# Relay_Board_Rev1-3_-_EasyEDA.net
KiCad netlist of a schematic drawn in EasyEDA
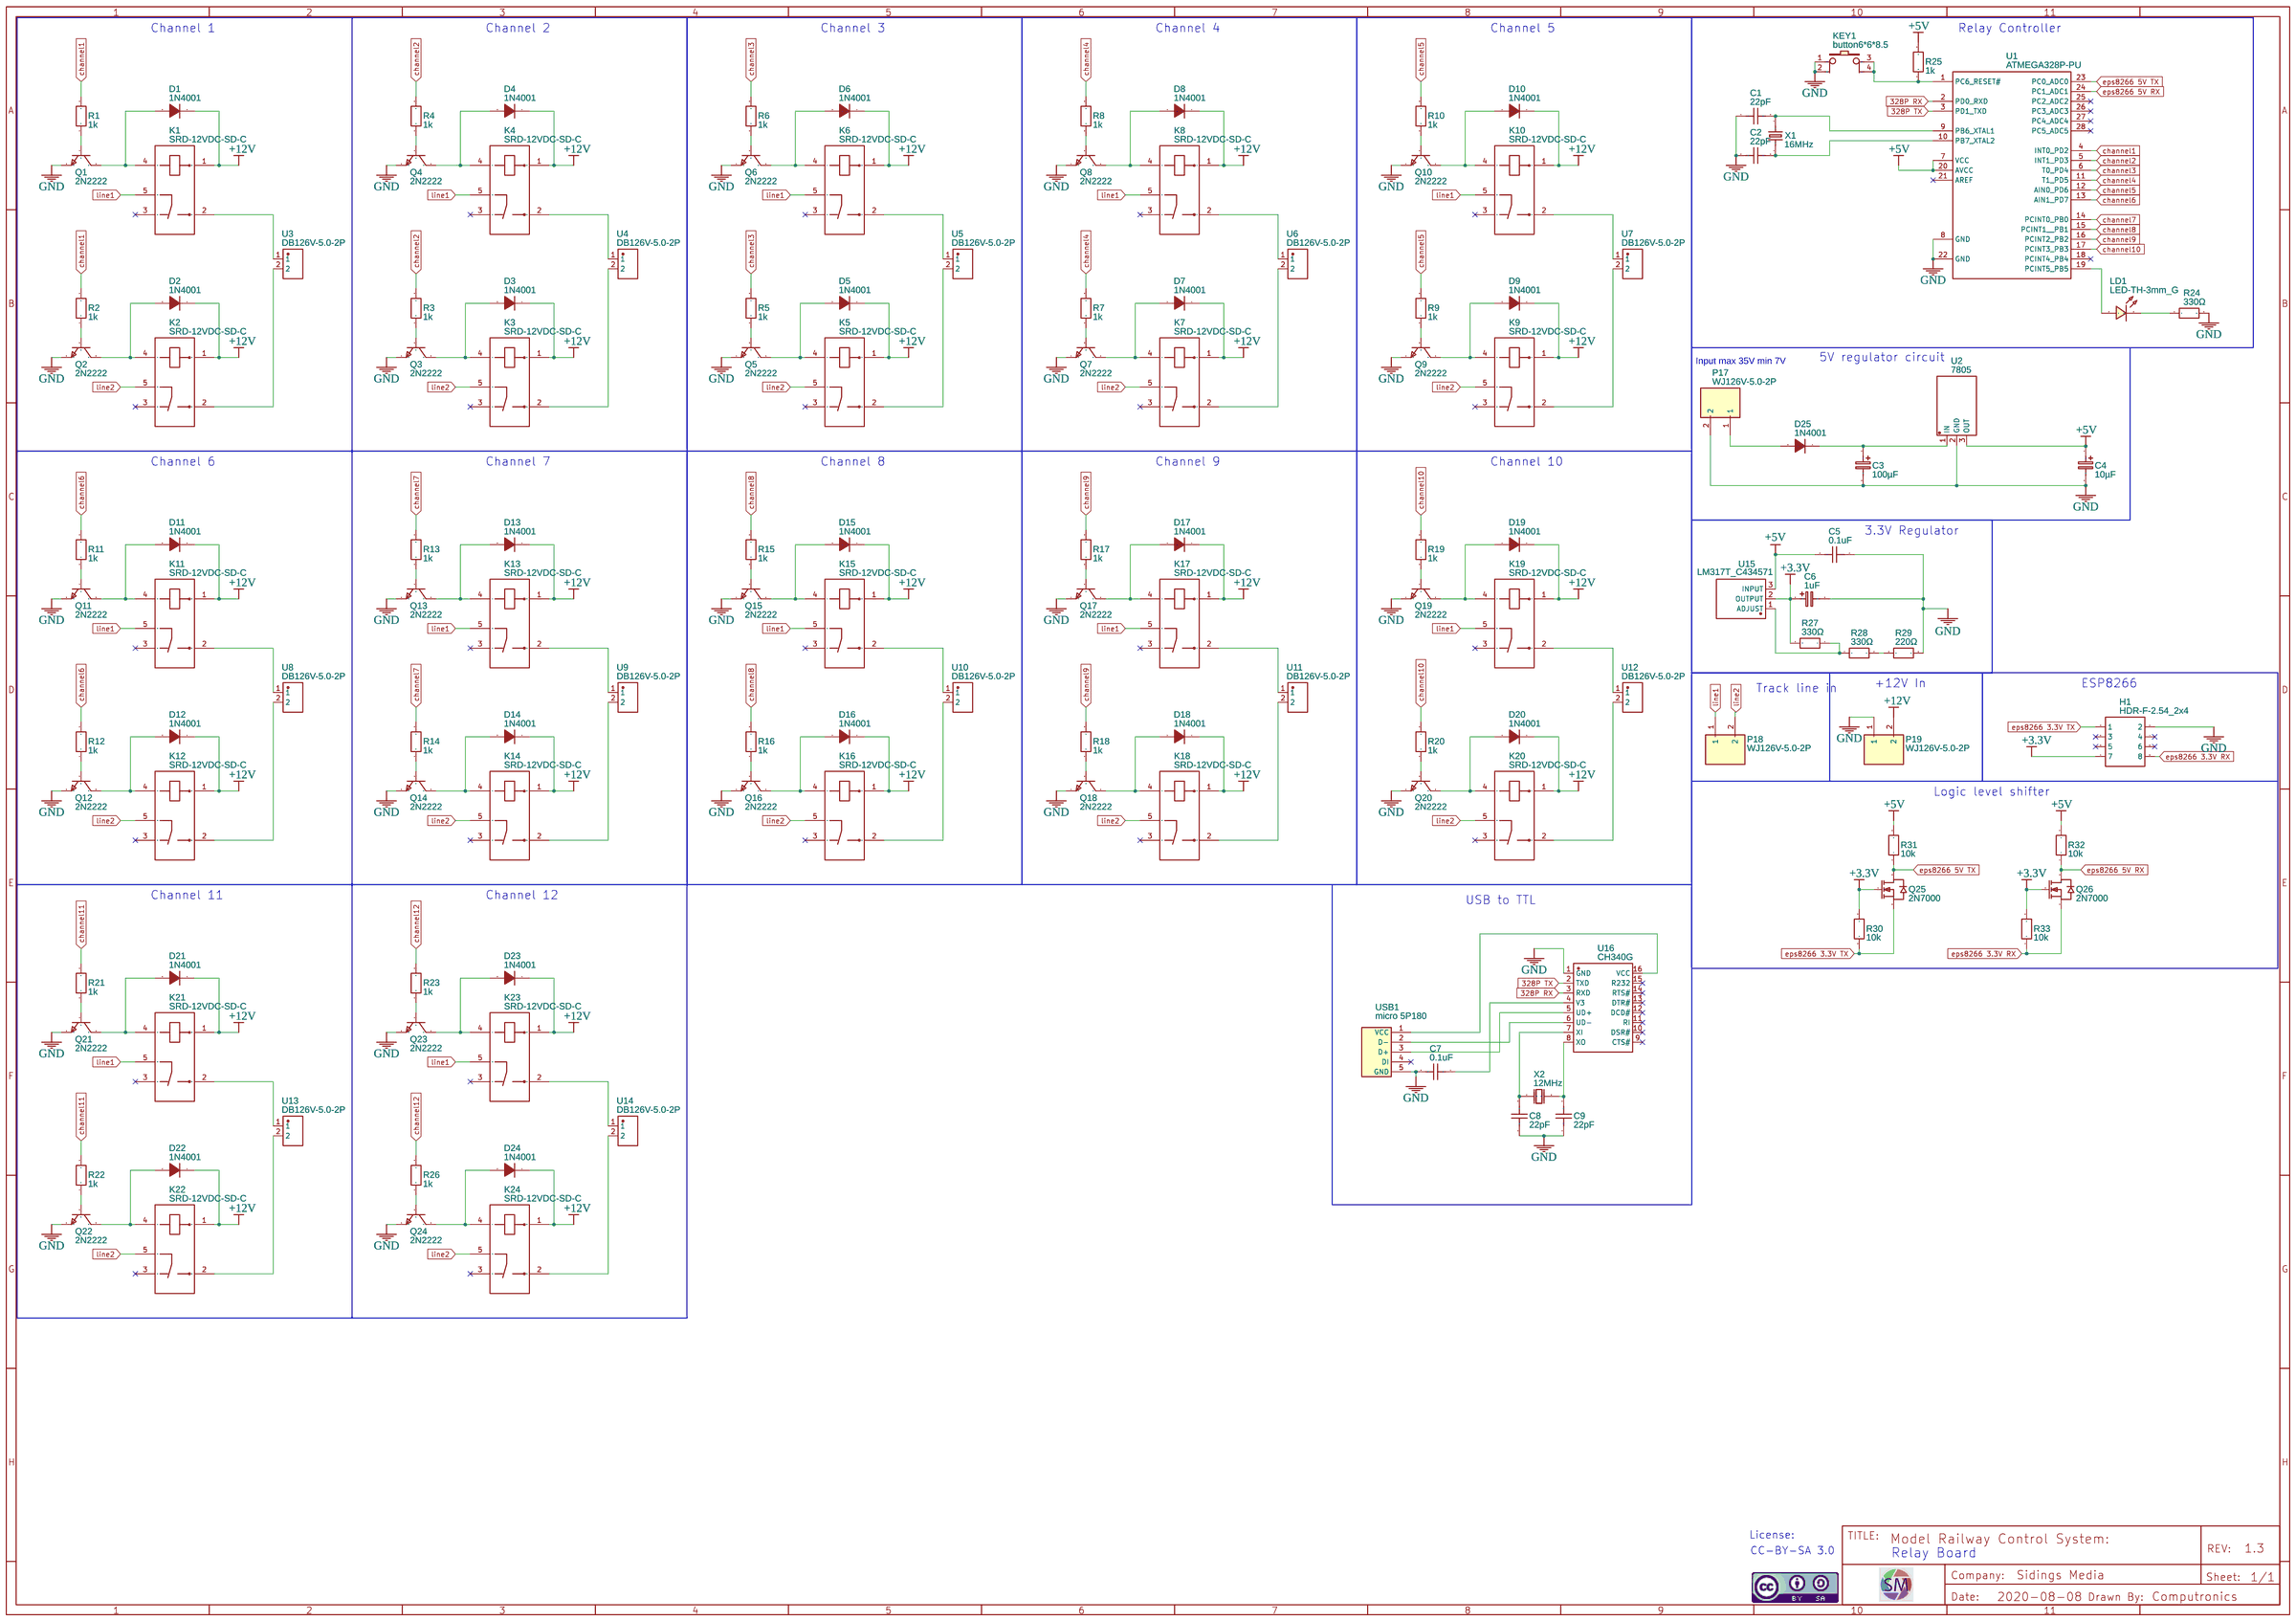
[diagram p0: schematic sheet]

(export (version "E")
  (design (tool "Eeschema 10.0.6"))
  (components
    (comp (ref "C1") (value "22pF") (libsource (lib "") (part "C_RAD-0.2_US")))
    (comp (ref "C2") (value "22pF") (libsource (lib "") (part "C_RAD-0.2_US")))
    (comp (ref "C3") (value "100µF") (libsource (lib "") (part "CE_TH_D3.0×F1.5_EU")))
    (comp (ref "C4") (value "10µF") (libsource (lib "") (part "CE_TH_D3.0×F1.5_EU_2")))
    (comp (ref "C5") (value "0.1uF") (libsource (lib "") (part "C_RAD-0.2_US_1")))
    (comp (ref "C6") (value "1uF") (libsource (lib "") (part "CE_TH_D3.0×F1.5_EU_1")))
    (comp (ref "C7") (value "0.1uF") (libsource (lib "") (part "C_RAD-0.2_US_1")))
    (comp (ref "C8") (value "22pF") (libsource (lib "") (part "C_RAD-0.2_US_2")))
    (comp (ref "C9") (value "22pF") (libsource (lib "") (part "C_RAD-0.2_US_2")))
    (comp (ref "D1")
      (value "1N4001")
      (fields (field (name "BOM_Supplier Part") "C82804"))
      (libsource (lib "") (part "1N4001"))
    )
    (comp (ref "D2")
      (value "1N4001")
      (fields (field (name "BOM_Supplier Part") "C82804"))
      (libsource (lib "") (part "1N4001"))
    )
    (comp (ref "D3")
      (value "1N4001")
      (fields (field (name "BOM_Supplier Part") "C82804"))
      (libsource (lib "") (part "1N4001"))
    )
    (comp (ref "D4")
      (value "1N4001")
      (fields (field (name "BOM_Supplier Part") "C82804"))
      (libsource (lib "") (part "1N4001"))
    )
    (comp (ref "D5")
      (value "1N4001")
      (fields (field (name "BOM_Supplier Part") "C82804"))
      (libsource (lib "") (part "1N4001"))
    )
    (comp (ref "D6")
      (value "1N4001")
      (fields (field (name "BOM_Supplier Part") "C82804"))
      (libsource (lib "") (part "1N4001"))
    )
    (comp (ref "D7")
      (value "1N4001")
      (fields (field (name "BOM_Supplier Part") "C82804"))
      (libsource (lib "") (part "1N4001"))
    )
    (comp (ref "D8")
      (value "1N4001")
      (fields (field (name "BOM_Supplier Part") "C82804"))
      (libsource (lib "") (part "1N4001"))
    )
    (comp (ref "D9")
      (value "1N4001")
      (fields (field (name "BOM_Supplier Part") "C82804"))
      (libsource (lib "") (part "1N4001"))
    )
    (comp (ref "D10")
      (value "1N4001")
      (fields (field (name "BOM_Supplier Part") "C82804"))
      (libsource (lib "") (part "1N4001"))
    )
    (comp (ref "D11")
      (value "1N4001")
      (fields (field (name "BOM_Supplier Part") "C82804"))
      (libsource (lib "") (part "1N4001"))
    )
    (comp (ref "D12")
      (value "1N4001")
      (fields (field (name "BOM_Supplier Part") "C82804"))
      (libsource (lib "") (part "1N4001"))
    )
    (comp (ref "D13")
      (value "1N4001")
      (fields (field (name "BOM_Supplier Part") "C82804"))
      (libsource (lib "") (part "1N4001"))
    )
    (comp (ref "D14")
      (value "1N4001")
      (fields (field (name "BOM_Supplier Part") "C82804"))
      (libsource (lib "") (part "1N4001"))
    )
    (comp (ref "D15")
      (value "1N4001")
      (fields (field (name "BOM_Supplier Part") "C82804"))
      (libsource (lib "") (part "1N4001"))
    )
    (comp (ref "D16")
      (value "1N4001")
      (fields (field (name "BOM_Supplier Part") "C82804"))
      (libsource (lib "") (part "1N4001"))
    )
    (comp (ref "D17")
      (value "1N4001")
      (fields (field (name "BOM_Supplier Part") "C82804"))
      (libsource (lib "") (part "1N4001"))
    )
    (comp (ref "D18")
      (value "1N4001")
      (fields (field (name "BOM_Supplier Part") "C82804"))
      (libsource (lib "") (part "1N4001"))
    )
    (comp (ref "D19")
      (value "1N4001")
      (fields (field (name "BOM_Supplier Part") "C82804"))
      (libsource (lib "") (part "1N4001"))
    )
    (comp (ref "D20")
      (value "1N4001")
      (fields (field (name "BOM_Supplier Part") "C82804"))
      (libsource (lib "") (part "1N4001"))
    )
    (comp (ref "D21")
      (value "1N4001")
      (fields (field (name "BOM_Supplier Part") "C82804"))
      (libsource (lib "") (part "1N4001"))
    )
    (comp (ref "D22")
      (value "1N4001")
      (fields (field (name "BOM_Supplier Part") "C82804"))
      (libsource (lib "") (part "1N4001"))
    )
    (comp (ref "D23")
      (value "1N4001")
      (fields (field (name "BOM_Supplier Part") "C82804"))
      (libsource (lib "") (part "1N4001"))
    )
    (comp (ref "D24")
      (value "1N4001")
      (fields (field (name "BOM_Supplier Part") "C82804"))
      (libsource (lib "") (part "1N4001"))
    )
    (comp (ref "D25")
      (value "1N4001")
      (fields (field (name "BOM_Supplier Part") "C82804"))
      (libsource (lib "") (part "1N4001"))
    )
    (comp (ref "H1")
      (value "HDR-F-2.54_2x4")
      (fields (field (name "BOM_Supplier Part") "C239344"))
      (libsource (lib "") (part "HDR-F-2.54_2x4"))
    )
    (comp (ref "K1")
      (value "SRD-12VDC-SD-C")
      (fields (field (name "BOM_Supplier Part") "C247843"))
      (libsource (lib "") (part "SRD-12VDC-SD-C"))
    )
    (comp (ref "K2")
      (value "SRD-12VDC-SD-C")
      (fields (field (name "BOM_Supplier Part") "C247843"))
      (libsource (lib "") (part "SRD-12VDC-SD-C"))
    )
    (comp (ref "K3")
      (value "SRD-12VDC-SD-C")
      (fields (field (name "BOM_Supplier Part") "C247843"))
      (libsource (lib "") (part "SRD-12VDC-SD-C"))
    )
    (comp (ref "K4")
      (value "SRD-12VDC-SD-C")
      (fields (field (name "BOM_Supplier Part") "C247843"))
      (libsource (lib "") (part "SRD-12VDC-SD-C"))
    )
    (comp (ref "K5")
      (value "SRD-12VDC-SD-C")
      (fields (field (name "BOM_Supplier Part") "C247843"))
      (libsource (lib "") (part "SRD-12VDC-SD-C"))
    )
    (comp (ref "K6")
      (value "SRD-12VDC-SD-C")
      (fields (field (name "BOM_Supplier Part") "C247843"))
      (libsource (lib "") (part "SRD-12VDC-SD-C"))
    )
    (comp (ref "K7")
      (value "SRD-12VDC-SD-C")
      (fields (field (name "BOM_Supplier Part") "C247843"))
      (libsource (lib "") (part "SRD-12VDC-SD-C"))
    )
    (comp (ref "K8")
      (value "SRD-12VDC-SD-C")
      (fields (field (name "BOM_Supplier Part") "C247843"))
      (libsource (lib "") (part "SRD-12VDC-SD-C"))
    )
    (comp (ref "K9")
      (value "SRD-12VDC-SD-C")
      (fields (field (name "BOM_Supplier Part") "C247843"))
      (libsource (lib "") (part "SRD-12VDC-SD-C"))
    )
    (comp (ref "K10")
      (value "SRD-12VDC-SD-C")
      (fields (field (name "BOM_Supplier Part") "C247843"))
      (libsource (lib "") (part "SRD-12VDC-SD-C"))
    )
    (comp (ref "K11")
      (value "SRD-12VDC-SD-C")
      (fields (field (name "BOM_Supplier Part") "C247843"))
      (libsource (lib "") (part "SRD-12VDC-SD-C"))
    )
    (comp (ref "K12")
      (value "SRD-12VDC-SD-C")
      (fields (field (name "BOM_Supplier Part") "C247843"))
      (libsource (lib "") (part "SRD-12VDC-SD-C"))
    )
    (comp (ref "K13")
      (value "SRD-12VDC-SD-C")
      (fields (field (name "BOM_Supplier Part") "C247843"))
      (libsource (lib "") (part "SRD-12VDC-SD-C"))
    )
    (comp (ref "K14")
      (value "SRD-12VDC-SD-C")
      (fields (field (name "BOM_Supplier Part") "C247843"))
      (libsource (lib "") (part "SRD-12VDC-SD-C"))
    )
    (comp (ref "K15")
      (value "SRD-12VDC-SD-C")
      (fields (field (name "BOM_Supplier Part") "C247843"))
      (libsource (lib "") (part "SRD-12VDC-SD-C"))
    )
    (comp (ref "K16")
      (value "SRD-12VDC-SD-C")
      (fields (field (name "BOM_Supplier Part") "C247843"))
      (libsource (lib "") (part "SRD-12VDC-SD-C"))
    )
    (comp (ref "K17")
      (value "SRD-12VDC-SD-C")
      (fields (field (name "BOM_Supplier Part") "C247843"))
      (libsource (lib "") (part "SRD-12VDC-SD-C"))
    )
    (comp (ref "K18")
      (value "SRD-12VDC-SD-C")
      (fields (field (name "BOM_Supplier Part") "C247843"))
      (libsource (lib "") (part "SRD-12VDC-SD-C"))
    )
    (comp (ref "K19")
      (value "SRD-12VDC-SD-C")
      (fields (field (name "BOM_Supplier Part") "C247843"))
      (libsource (lib "") (part "SRD-12VDC-SD-C"))
    )
    (comp (ref "K20")
      (value "SRD-12VDC-SD-C")
      (fields (field (name "BOM_Supplier Part") "C247843"))
      (libsource (lib "") (part "SRD-12VDC-SD-C"))
    )
    (comp (ref "K21")
      (value "SRD-12VDC-SD-C")
      (fields (field (name "BOM_Supplier Part") "C247843"))
      (libsource (lib "") (part "SRD-12VDC-SD-C"))
    )
    (comp (ref "K22")
      (value "SRD-12VDC-SD-C")
      (fields (field (name "BOM_Supplier Part") "C247843"))
      (libsource (lib "") (part "SRD-12VDC-SD-C"))
    )
    (comp (ref "K23")
      (value "SRD-12VDC-SD-C")
      (fields (field (name "BOM_Supplier Part") "C247843"))
      (libsource (lib "") (part "SRD-12VDC-SD-C"))
    )
    (comp (ref "K24")
      (value "SRD-12VDC-SD-C")
      (fields (field (name "BOM_Supplier Part") "C247843"))
      (libsource (lib "") (part "SRD-12VDC-SD-C"))
    )
    (comp (ref "KEY1")
      (value "button6*6*8.5")
      (fields (field (name "BOM_Supplier Part") "C59980"))
      (libsource (lib "") (part "button6*6*8.5"))
    )
    (comp (ref "LD1")
      (value "LED-TH-3mm_G")
      (fields
        (field (name "BOM_Manufacturer Part") "204-10SYGD/S530-E3")
        (field (name "BOM_Supplier Part") "C85161")
      )
      (libsource (lib "") (part "LED-TH-3mm_G"))
    )
    (comp (ref "P17")
      (value "WJ126V-5.0-2P")
      (fields (field (name "BOM_Supplier Part") "C8404"))
      (libsource (lib "") (part "WJ126V-5.0-2P_1"))
    )
    (comp (ref "P18")
      (value "WJ126V-5.0-2P")
      (fields (field (name "BOM_Supplier Part") "C8404"))
      (libsource (lib "") (part "WJ126V-5.0-2P"))
    )
    (comp (ref "P19")
      (value "WJ126V-5.0-2P")
      (fields (field (name "BOM_Supplier Part") "C8404"))
      (libsource (lib "") (part "WJ126V-5.0-2P"))
    )
    (comp (ref "Q1")
      (value "2N2222")
      (fields (field (name "BOM_Supplier Part") "C118536"))
      (libsource (lib "") (part "2N2222"))
    )
    (comp (ref "Q2")
      (value "2N2222")
      (fields (field (name "BOM_Supplier Part") "C118536"))
      (libsource (lib "") (part "2N2222"))
    )
    (comp (ref "Q3")
      (value "2N2222")
      (fields (field (name "BOM_Supplier Part") "C118536"))
      (libsource (lib "") (part "2N2222"))
    )
    (comp (ref "Q4")
      (value "2N2222")
      (fields (field (name "BOM_Supplier Part") "C118536"))
      (libsource (lib "") (part "2N2222"))
    )
    (comp (ref "Q5")
      (value "2N2222")
      (fields (field (name "BOM_Supplier Part") "C118536"))
      (libsource (lib "") (part "2N2222"))
    )
    (comp (ref "Q6")
      (value "2N2222")
      (fields (field (name "BOM_Supplier Part") "C118536"))
      (libsource (lib "") (part "2N2222"))
    )
    (comp (ref "Q7")
      (value "2N2222")
      (fields (field (name "BOM_Supplier Part") "C118536"))
      (libsource (lib "") (part "2N2222"))
    )
    (comp (ref "Q8")
      (value "2N2222")
      (fields (field (name "BOM_Supplier Part") "C118536"))
      (libsource (lib "") (part "2N2222"))
    )
    (comp (ref "Q9")
      (value "2N2222")
      (fields (field (name "BOM_Supplier Part") "C118536"))
      (libsource (lib "") (part "2N2222"))
    )
    (comp (ref "Q10")
      (value "2N2222")
      (fields (field (name "BOM_Supplier Part") "C118536"))
      (libsource (lib "") (part "2N2222"))
    )
    (comp (ref "Q11")
      (value "2N2222")
      (fields (field (name "BOM_Supplier Part") "C118536"))
      (libsource (lib "") (part "2N2222"))
    )
    (comp (ref "Q12")
      (value "2N2222")
      (fields (field (name "BOM_Supplier Part") "C118536"))
      (libsource (lib "") (part "2N2222"))
    )
    (comp (ref "Q13")
      (value "2N2222")
      (fields (field (name "BOM_Supplier Part") "C118536"))
      (libsource (lib "") (part "2N2222"))
    )
    (comp (ref "Q14")
      (value "2N2222")
      (fields (field (name "BOM_Supplier Part") "C118536"))
      (libsource (lib "") (part "2N2222"))
    )
    (comp (ref "Q15")
      (value "2N2222")
      (fields (field (name "BOM_Supplier Part") "C118536"))
      (libsource (lib "") (part "2N2222"))
    )
    (comp (ref "Q16")
      (value "2N2222")
      (fields (field (name "BOM_Supplier Part") "C118536"))
      (libsource (lib "") (part "2N2222"))
    )
    (comp (ref "Q17")
      (value "2N2222")
      (fields (field (name "BOM_Supplier Part") "C118536"))
      (libsource (lib "") (part "2N2222"))
    )
    (comp (ref "Q18")
      (value "2N2222")
      (fields (field (name "BOM_Supplier Part") "C118536"))
      (libsource (lib "") (part "2N2222"))
    )
    (comp (ref "Q19")
      (value "2N2222")
      (fields (field (name "BOM_Supplier Part") "C118536"))
      (libsource (lib "") (part "2N2222"))
    )
    (comp (ref "Q20")
      (value "2N2222")
      (fields (field (name "BOM_Supplier Part") "C118536"))
      (libsource (lib "") (part "2N2222"))
    )
    (comp (ref "Q21")
      (value "2N2222")
      (fields (field (name "BOM_Supplier Part") "C118536"))
      (libsource (lib "") (part "2N2222"))
    )
    (comp (ref "Q22")
      (value "2N2222")
      (fields (field (name "BOM_Supplier Part") "C118536"))
      (libsource (lib "") (part "2N2222"))
    )
    (comp (ref "Q23")
      (value "2N2222")
      (fields (field (name "BOM_Supplier Part") "C118536"))
      (libsource (lib "") (part "2N2222"))
    )
    (comp (ref "Q24")
      (value "2N2222")
      (fields (field (name "BOM_Supplier Part") "C118536"))
      (libsource (lib "") (part "2N2222"))
    )
    (comp (ref "Q25")
      (value "2N7000")
      (fields (field (name "BOM_Supplier Part") "C9114"))
      (libsource (lib "") (part "2N7000"))
    )
    (comp (ref "Q26")
      (value "2N7000")
      (fields (field (name "BOM_Supplier Part") "C9114"))
      (libsource (lib "") (part "2N7000"))
    )
    (comp (ref "R1") (value "1k") (libsource (lib "") (part "R_AXIAL-0.4_EU")))
    (comp (ref "R2") (value "1k") (libsource (lib "") (part "R_AXIAL-0.4_EU")))
    (comp (ref "R3") (value "1k") (libsource (lib "") (part "R_AXIAL-0.4_EU")))
    (comp (ref "R4") (value "1k") (libsource (lib "") (part "R_AXIAL-0.4_EU")))
    (comp (ref "R5") (value "1k") (libsource (lib "") (part "R_AXIAL-0.4_EU")))
    (comp (ref "R6") (value "1k") (libsource (lib "") (part "R_AXIAL-0.4_EU")))
    (comp (ref "R7") (value "1k") (libsource (lib "") (part "R_AXIAL-0.4_EU")))
    (comp (ref "R8") (value "1k") (libsource (lib "") (part "R_AXIAL-0.4_EU")))
    (comp (ref "R9") (value "1k") (libsource (lib "") (part "R_AXIAL-0.4_EU")))
    (comp (ref "R10") (value "1k") (libsource (lib "") (part "R_AXIAL-0.4_EU")))
    (comp (ref "R11") (value "1k") (libsource (lib "") (part "R_AXIAL-0.4_EU")))
    (comp (ref "R12") (value "1k") (libsource (lib "") (part "R_AXIAL-0.4_EU")))
    (comp (ref "R13") (value "1k") (libsource (lib "") (part "R_AXIAL-0.4_EU")))
    (comp (ref "R14") (value "1k") (libsource (lib "") (part "R_AXIAL-0.4_EU")))
    (comp (ref "R15") (value "1k") (libsource (lib "") (part "R_AXIAL-0.4_EU")))
    (comp (ref "R16") (value "1k") (libsource (lib "") (part "R_AXIAL-0.4_EU")))
    (comp (ref "R17") (value "1k") (libsource (lib "") (part "R_AXIAL-0.4_EU")))
    (comp (ref "R18") (value "1k") (libsource (lib "") (part "R_AXIAL-0.4_EU")))
    (comp (ref "R19") (value "1k") (libsource (lib "") (part "R_AXIAL-0.4_EU")))
    (comp (ref "R20") (value "1k") (libsource (lib "") (part "R_AXIAL-0.4_EU")))
    (comp (ref "R21") (value "1k") (libsource (lib "") (part "R_AXIAL-0.4_EU")))
    (comp (ref "R22") (value "1k") (libsource (lib "") (part "R_AXIAL-0.4_EU")))
    (comp (ref "R23") (value "1k") (libsource (lib "") (part "R_AXIAL-0.4_EU")))
    (comp (ref "R24") (value "330Ω") (libsource (lib "") (part "R_AXIAL-0.4_EU_1")))
    (comp (ref "R25") (value "1k") (libsource (lib "") (part "R_AXIAL-0.4_EU")))
    (comp (ref "R26") (value "1k") (libsource (lib "") (part "R_AXIAL-0.4_EU")))
    (comp (ref "R27") (value "330Ω") (libsource (lib "") (part "R_AXIAL-0.4_EU_2")))
    (comp (ref "R28") (value "330Ω") (libsource (lib "") (part "R_AXIAL-0.4_EU_1")))
    (comp (ref "R29") (value "220Ω") (libsource (lib "") (part "R_AXIAL-0.4_EU_1")))
    (comp (ref "R30") (value "10k") (libsource (lib "") (part "R_AXIAL-0.4_EU")))
    (comp (ref "R31") (value "10k") (libsource (lib "") (part "R_AXIAL-0.4_EU")))
    (comp (ref "R32") (value "10k") (libsource (lib "") (part "R_AXIAL-0.4_EU")))
    (comp (ref "R33") (value "10k") (libsource (lib "") (part "R_AXIAL-0.4_EU")))
    (comp (ref "U1")
      (value "ATMEGA328P-PU")
      (fields (field (name "BOM_Supplier Part") "C33901"))
      (libsource (lib "") (part "ATMEGA328P-PU"))
    )
    (comp (ref "U2")
      (value "7805")
      (fields (field (name "BOM_Supplier Part") "C305416"))
      (libsource (lib "") (part "7805"))
    )
    (comp (ref "U3")
      (value "DB126V-5.0-2P")
      (fields (field (name "BOM_Supplier Part") "C395849"))
      (libsource (lib "") (part "DB126V-5.0-2P"))
    )
    (comp (ref "U4")
      (value "DB126V-5.0-2P")
      (fields (field (name "BOM_Supplier Part") "C395849"))
      (libsource (lib "") (part "DB126V-5.0-2P"))
    )
    (comp (ref "U5")
      (value "DB126V-5.0-2P")
      (fields (field (name "BOM_Supplier Part") "C395849"))
      (libsource (lib "") (part "DB126V-5.0-2P"))
    )
    (comp (ref "U6")
      (value "DB126V-5.0-2P")
      (fields (field (name "BOM_Supplier Part") "C395849"))
      (libsource (lib "") (part "DB126V-5.0-2P"))
    )
    (comp (ref "U7")
      (value "DB126V-5.0-2P")
      (fields (field (name "BOM_Supplier Part") "C395849"))
      (libsource (lib "") (part "DB126V-5.0-2P"))
    )
    (comp (ref "U8")
      (value "DB126V-5.0-2P")
      (fields (field (name "BOM_Supplier Part") "C395849"))
      (libsource (lib "") (part "DB126V-5.0-2P"))
    )
    (comp (ref "U9")
      (value "DB126V-5.0-2P")
      (fields (field (name "BOM_Supplier Part") "C395849"))
      (libsource (lib "") (part "DB126V-5.0-2P"))
    )
    (comp (ref "U10")
      (value "DB126V-5.0-2P")
      (fields (field (name "BOM_Supplier Part") "C395849"))
      (libsource (lib "") (part "DB126V-5.0-2P"))
    )
    (comp (ref "U11")
      (value "DB126V-5.0-2P")
      (fields (field (name "BOM_Supplier Part") "C395849"))
      (libsource (lib "") (part "DB126V-5.0-2P"))
    )
    (comp (ref "U12")
      (value "DB126V-5.0-2P")
      (fields (field (name "BOM_Supplier Part") "C395849"))
      (libsource (lib "") (part "DB126V-5.0-2P"))
    )
    (comp (ref "U13")
      (value "DB126V-5.0-2P")
      (fields (field (name "BOM_Supplier Part") "C395849"))
      (libsource (lib "") (part "DB126V-5.0-2P"))
    )
    (comp (ref "U14")
      (value "DB126V-5.0-2P")
      (fields (field (name "BOM_Supplier Part") "C395849"))
      (libsource (lib "") (part "DB126V-5.0-2P"))
    )
    (comp (ref "U15")
      (value "LM317T_C434571")
      (fields (field (name "BOM_Manufacturer Part") "LM317T") (field (name "BOM_Supplier Part") "C434571"))
      (libsource (lib "") (part "LM317T_C434571"))
    )
    (comp (ref "U16")
      (value "CH340G")
      (fields (field (name "BOM_Supplier Part") "C14267"))
      (libsource (lib "") (part "CH340G"))
    )
    (comp (ref "USB1")
      (value "micro 5P180")
      (fields (field (name "BOM_Supplier Part") "C40941"))
      (libsource (lib "") (part "micro 5P180"))
    )
    (comp (ref "X1")
      (value "16MHz")
      (fields
        (field (name "BOM_Manufacturer Part") "XIHCELNANF-16MHZ")
        (field (name "BOM_Supplier Part") "C295075")
      )
      (libsource (lib "") (part "XIHCELNANF-16MHZ"))
    )
    (comp (ref "X2")
      (value "12MHz")
      (fields
        (field (name "BOM_Manufacturer Part") "49S-12.00-20-20-20/A")
        (field (name "BOM_Supplier Part") "C240914")
      )
      (libsource (lib "") (part "49S-12.00-20-20-20/A"))
    )
  )
  (nets
    (net (code "1") (name "+3.3V") (class "Default")
      (node (ref "C6") (pin "1") (pinfunction "1_1") (pintype "unspecified"))
      (node (ref "H1") (pin "7") (pinfunction "7_7") (pintype "unspecified"))
      (node (ref "Q25") (pin "2") (pinfunction "G_2") (pintype "unspecified"))
      (node (ref "Q26") (pin "2") (pinfunction "G_2") (pintype "unspecified"))
      (node (ref "R27") (pin "2") (pinfunction "2_2") (pintype "unspecified"))
      (node (ref "R30") (pin "2") (pinfunction "2_2") (pintype "unspecified"))
      (node (ref "R33") (pin "2") (pinfunction "2_2") (pintype "unspecified"))
      (node (ref "U15") (pin "2") (pinfunction "OUTPUT_2") (pintype "unspecified"))
    )
    (net (code "2") (name "+5V") (class "Default")
      (node (ref "C4") (pin "1") (pinfunction "1_1") (pintype "unspecified"))
      (node (ref "C5") (pin "2") (pinfunction "2_2") (pintype "unspecified"))
      (node (ref "R25") (pin "2") (pinfunction "2_2") (pintype "unspecified"))
      (node (ref "R31") (pin "2") (pinfunction "2_2") (pintype "unspecified"))
      (node (ref "R32") (pin "2") (pinfunction "2_2") (pintype "unspecified"))
      (node (ref "U1") (pin "20") (pinfunction "AVCC_20") (pintype "passive"))
      (node (ref "U1") (pin "7") (pinfunction "VCC_7") (pintype "passive"))
      (node (ref "U15") (pin "3") (pinfunction "INPUT_3") (pintype "unspecified"))
      (node (ref "U2") (pin "3") (pinfunction "OUT_3") (pintype "unspecified"))
    )
    (net (code "3") (name "+12V") (class "Default")
      (node (ref "D1") (pin "1") (pinfunction "K_1") (pintype "unspecified"))
      (node (ref "D10") (pin "1") (pinfunction "K_1") (pintype "unspecified"))
      (node (ref "D11") (pin "1") (pinfunction "K_1") (pintype "unspecified"))
      (node (ref "D12") (pin "1") (pinfunction "K_1") (pintype "unspecified"))
      (node (ref "D13") (pin "1") (pinfunction "K_1") (pintype "unspecified"))
      (node (ref "D14") (pin "1") (pinfunction "K_1") (pintype "unspecified"))
      (node (ref "D15") (pin "1") (pinfunction "K_1") (pintype "unspecified"))
      (node (ref "D16") (pin "1") (pinfunction "K_1") (pintype "unspecified"))
      (node (ref "D17") (pin "1") (pinfunction "K_1") (pintype "unspecified"))
      (node (ref "D18") (pin "1") (pinfunction "K_1") (pintype "unspecified"))
      (node (ref "D19") (pin "1") (pinfunction "K_1") (pintype "unspecified"))
      (node (ref "D2") (pin "1") (pinfunction "K_1") (pintype "unspecified"))
      (node (ref "D20") (pin "1") (pinfunction "K_1") (pintype "unspecified"))
      (node (ref "D21") (pin "1") (pinfunction "K_1") (pintype "unspecified"))
      (node (ref "D22") (pin "1") (pinfunction "K_1") (pintype "unspecified"))
      (node (ref "D23") (pin "1") (pinfunction "K_1") (pintype "unspecified"))
      (node (ref "D24") (pin "1") (pinfunction "K_1") (pintype "unspecified"))
      (node (ref "D3") (pin "1") (pinfunction "K_1") (pintype "unspecified"))
      (node (ref "D4") (pin "1") (pinfunction "K_1") (pintype "unspecified"))
      (node (ref "D5") (pin "1") (pinfunction "K_1") (pintype "unspecified"))
      (node (ref "D6") (pin "1") (pinfunction "K_1") (pintype "unspecified"))
      (node (ref "D7") (pin "1") (pinfunction "K_1") (pintype "unspecified"))
      (node (ref "D8") (pin "1") (pinfunction "K_1") (pintype "unspecified"))
      (node (ref "D9") (pin "1") (pinfunction "K_1") (pintype "unspecified"))
      (node (ref "K1") (pin "1") (pinfunction "1_1") (pintype "input"))
      (node (ref "K10") (pin "1") (pinfunction "1_1") (pintype "input"))
      (node (ref "K11") (pin "1") (pinfunction "1_1") (pintype "input"))
      (node (ref "K12") (pin "1") (pinfunction "1_1") (pintype "input"))
      (node (ref "K13") (pin "1") (pinfunction "1_1") (pintype "input"))
      (node (ref "K14") (pin "1") (pinfunction "1_1") (pintype "input"))
      (node (ref "K15") (pin "1") (pinfunction "1_1") (pintype "input"))
      (node (ref "K16") (pin "1") (pinfunction "1_1") (pintype "input"))
      (node (ref "K17") (pin "1") (pinfunction "1_1") (pintype "input"))
      (node (ref "K18") (pin "1") (pinfunction "1_1") (pintype "input"))
      (node (ref "K19") (pin "1") (pinfunction "1_1") (pintype "input"))
      (node (ref "K2") (pin "1") (pinfunction "1_1") (pintype "input"))
      (node (ref "K20") (pin "1") (pinfunction "1_1") (pintype "input"))
      (node (ref "K21") (pin "1") (pinfunction "1_1") (pintype "input"))
      (node (ref "K22") (pin "1") (pinfunction "1_1") (pintype "input"))
      (node (ref "K23") (pin "1") (pinfunction "1_1") (pintype "input"))
      (node (ref "K24") (pin "1") (pinfunction "1_1") (pintype "input"))
      (node (ref "K3") (pin "1") (pinfunction "1_1") (pintype "input"))
      (node (ref "K4") (pin "1") (pinfunction "1_1") (pintype "input"))
      (node (ref "K5") (pin "1") (pinfunction "1_1") (pintype "input"))
      (node (ref "K6") (pin "1") (pinfunction "1_1") (pintype "input"))
      (node (ref "K7") (pin "1") (pinfunction "1_1") (pintype "input"))
      (node (ref "K8") (pin "1") (pinfunction "1_1") (pintype "input"))
      (node (ref "K9") (pin "1") (pinfunction "1_1") (pintype "input"))
      (node (ref "P19") (pin "2") (pinfunction "2_2") (pintype "input"))
    )
    (net (code "4") (name "328P RX") (class "Default")
      (node (ref "U1") (pin "2") (pinfunction "PD0_RXD_2") (pintype "bidirectional"))
      (node (ref "U16") (pin "3") (pinfunction "RXD_3") (pintype "unspecified"))
    )
    (net (code "5") (name "328P TX") (class "Default")
      (node (ref "U1") (pin "3") (pinfunction "PD1_TXD_3") (pintype "bidirectional"))
      (node (ref "U16") (pin "2") (pinfunction "TXD_2") (pintype "unspecified"))
    )
    (net (code "6") (name "GND") (class "Default")
      (node (ref "C1") (pin "1") (pinfunction "1_1") (pintype "unspecified"))
      (node (ref "C2") (pin "1") (pinfunction "1_1") (pintype "unspecified"))
      (node (ref "C3") (pin "2") (pinfunction "2_2") (pintype "unspecified"))
      (node (ref "C4") (pin "2") (pinfunction "2_2") (pintype "unspecified"))
      (node (ref "C5") (pin "1") (pinfunction "1_1") (pintype "unspecified"))
      (node (ref "C6") (pin "2") (pinfunction "2_2") (pintype "unspecified"))
      (node (ref "C7") (pin "2") (pinfunction "2_2") (pintype "unspecified"))
      (node (ref "C8") (pin "1") (pinfunction "1_1") (pintype "unspecified"))
      (node (ref "C9") (pin "1") (pinfunction "1_1") (pintype "unspecified"))
      (node (ref "H1") (pin "2") (pinfunction "2_2") (pintype "unspecified"))
      (node (ref "KEY1") (pin "1") (pinfunction "1_1") (pintype "input"))
      (node (ref "KEY1") (pin "2") (pinfunction "2_2") (pintype "input"))
      (node (ref "P17") (pin "2") (pinfunction "2_2") (pintype "input"))
      (node (ref "P19") (pin "1") (pinfunction "1_1") (pintype "input"))
      (node (ref "Q1") (pin "1") (pinfunction "E_1") (pintype "unspecified"))
      (node (ref "Q10") (pin "1") (pinfunction "E_1") (pintype "unspecified"))
      (node (ref "Q11") (pin "1") (pinfunction "E_1") (pintype "unspecified"))
      (node (ref "Q12") (pin "1") (pinfunction "E_1") (pintype "unspecified"))
      (node (ref "Q13") (pin "1") (pinfunction "E_1") (pintype "unspecified"))
      (node (ref "Q14") (pin "1") (pinfunction "E_1") (pintype "unspecified"))
      (node (ref "Q15") (pin "1") (pinfunction "E_1") (pintype "unspecified"))
      (node (ref "Q16") (pin "1") (pinfunction "E_1") (pintype "unspecified"))
      (node (ref "Q17") (pin "1") (pinfunction "E_1") (pintype "unspecified"))
      (node (ref "Q18") (pin "1") (pinfunction "E_1") (pintype "unspecified"))
      (node (ref "Q19") (pin "1") (pinfunction "E_1") (pintype "unspecified"))
      (node (ref "Q2") (pin "1") (pinfunction "E_1") (pintype "unspecified"))
      (node (ref "Q20") (pin "1") (pinfunction "E_1") (pintype "unspecified"))
      (node (ref "Q21") (pin "1") (pinfunction "E_1") (pintype "unspecified"))
      (node (ref "Q22") (pin "1") (pinfunction "E_1") (pintype "unspecified"))
      (node (ref "Q23") (pin "1") (pinfunction "E_1") (pintype "unspecified"))
      (node (ref "Q24") (pin "1") (pinfunction "E_1") (pintype "unspecified"))
      (node (ref "Q3") (pin "1") (pinfunction "E_1") (pintype "unspecified"))
      (node (ref "Q4") (pin "1") (pinfunction "E_1") (pintype "unspecified"))
      (node (ref "Q5") (pin "1") (pinfunction "E_1") (pintype "unspecified"))
      (node (ref "Q6") (pin "1") (pinfunction "E_1") (pintype "unspecified"))
      (node (ref "Q7") (pin "1") (pinfunction "E_1") (pintype "unspecified"))
      (node (ref "Q8") (pin "1") (pinfunction "E_1") (pintype "unspecified"))
      (node (ref "Q9") (pin "1") (pinfunction "E_1") (pintype "unspecified"))
      (node (ref "R24") (pin "2") (pinfunction "2_2") (pintype "unspecified"))
      (node (ref "R29") (pin "2") (pinfunction "2_2") (pintype "unspecified"))
      (node (ref "U1") (pin "22") (pinfunction "GND_22") (pintype "passive"))
      (node (ref "U1") (pin "8") (pinfunction "GND_8") (pintype "passive"))
      (node (ref "U16") (pin "1") (pinfunction "GND_1") (pintype "unspecified"))
      (node (ref "U2") (pin "2") (pinfunction "GND_2") (pintype "unspecified"))
      (node (ref "USB1") (pin "5") (pinfunction "GND_5") (pintype "input"))
    )
    (net (code "7") (name "Net-(D1-A)") (class "Default")
      (node (ref "D1") (pin "2") (pinfunction "A_2") (pintype "unspecified"))
      (node (ref "K1") (pin "4") (pinfunction "4_4") (pintype "input"))
      (node (ref "Q1") (pin "3") (pinfunction "C_3") (pintype "unspecified"))
    )
    (net (code "8") (name "Net-(D2-A)") (class "Default")
      (node (ref "D2") (pin "2") (pinfunction "A_2") (pintype "unspecified"))
      (node (ref "K2") (pin "4") (pinfunction "4_4") (pintype "input"))
      (node (ref "Q2") (pin "3") (pinfunction "C_3") (pintype "unspecified"))
    )
    (net (code "9") (name "Net-(D3-A)") (class "Default")
      (node (ref "D3") (pin "2") (pinfunction "A_2") (pintype "unspecified"))
      (node (ref "K3") (pin "4") (pinfunction "4_4") (pintype "input"))
      (node (ref "Q3") (pin "3") (pinfunction "C_3") (pintype "unspecified"))
    )
    (net (code "10") (name "Net-(D4-A)") (class "Default")
      (node (ref "D4") (pin "2") (pinfunction "A_2") (pintype "unspecified"))
      (node (ref "K4") (pin "4") (pinfunction "4_4") (pintype "input"))
      (node (ref "Q4") (pin "3") (pinfunction "C_3") (pintype "unspecified"))
    )
    (net (code "11") (name "Net-(D5-A)") (class "Default")
      (node (ref "D5") (pin "2") (pinfunction "A_2") (pintype "unspecified"))
      (node (ref "K5") (pin "4") (pinfunction "4_4") (pintype "input"))
      (node (ref "Q5") (pin "3") (pinfunction "C_3") (pintype "unspecified"))
    )
    (net (code "12") (name "Net-(D6-A)") (class "Default")
      (node (ref "D6") (pin "2") (pinfunction "A_2") (pintype "unspecified"))
      (node (ref "K6") (pin "4") (pinfunction "4_4") (pintype "input"))
      (node (ref "Q6") (pin "3") (pinfunction "C_3") (pintype "unspecified"))
    )
    (net (code "13") (name "Net-(D7-A)") (class "Default")
      (node (ref "D7") (pin "2") (pinfunction "A_2") (pintype "unspecified"))
      (node (ref "K7") (pin "4") (pinfunction "4_4") (pintype "input"))
      (node (ref "Q7") (pin "3") (pinfunction "C_3") (pintype "unspecified"))
    )
    (net (code "14") (name "Net-(D8-A)") (class "Default")
      (node (ref "D8") (pin "2") (pinfunction "A_2") (pintype "unspecified"))
      (node (ref "K8") (pin "4") (pinfunction "4_4") (pintype "input"))
      (node (ref "Q8") (pin "3") (pinfunction "C_3") (pintype "unspecified"))
    )
    (net (code "15") (name "Net-(D9-A)") (class "Default")
      (node (ref "D9") (pin "2") (pinfunction "A_2") (pintype "unspecified"))
      (node (ref "K9") (pin "4") (pinfunction "4_4") (pintype "input"))
      (node (ref "Q9") (pin "3") (pinfunction "C_3") (pintype "unspecified"))
    )
    (net (code "16") (name "Net-(D10-A)") (class "Default")
      (node (ref "D10") (pin "2") (pinfunction "A_2") (pintype "unspecified"))
      (node (ref "K10") (pin "4") (pinfunction "4_4") (pintype "input"))
      (node (ref "Q10") (pin "3") (pinfunction "C_3") (pintype "unspecified"))
    )
    (net (code "17") (name "Net-(D11-A)") (class "Default")
      (node (ref "D11") (pin "2") (pinfunction "A_2") (pintype "unspecified"))
      (node (ref "K11") (pin "4") (pinfunction "4_4") (pintype "input"))
      (node (ref "Q11") (pin "3") (pinfunction "C_3") (pintype "unspecified"))
    )
    (net (code "18") (name "Net-(D12-A)") (class "Default")
      (node (ref "D12") (pin "2") (pinfunction "A_2") (pintype "unspecified"))
      (node (ref "K12") (pin "4") (pinfunction "4_4") (pintype "input"))
      (node (ref "Q12") (pin "3") (pinfunction "C_3") (pintype "unspecified"))
    )
    (net (code "19") (name "Net-(D13-A)") (class "Default")
      (node (ref "D13") (pin "2") (pinfunction "A_2") (pintype "unspecified"))
      (node (ref "K13") (pin "4") (pinfunction "4_4") (pintype "input"))
      (node (ref "Q13") (pin "3") (pinfunction "C_3") (pintype "unspecified"))
    )
    (net (code "20") (name "Net-(D14-A)") (class "Default")
      (node (ref "D14") (pin "2") (pinfunction "A_2") (pintype "unspecified"))
      (node (ref "K14") (pin "4") (pinfunction "4_4") (pintype "input"))
      (node (ref "Q14") (pin "3") (pinfunction "C_3") (pintype "unspecified"))
    )
    (net (code "21") (name "Net-(D15-A)") (class "Default")
      (node (ref "D15") (pin "2") (pinfunction "A_2") (pintype "unspecified"))
      (node (ref "K15") (pin "4") (pinfunction "4_4") (pintype "input"))
      (node (ref "Q15") (pin "3") (pinfunction "C_3") (pintype "unspecified"))
    )
    (net (code "22") (name "Net-(D16-A)") (class "Default")
      (node (ref "D16") (pin "2") (pinfunction "A_2") (pintype "unspecified"))
      (node (ref "K16") (pin "4") (pinfunction "4_4") (pintype "input"))
      (node (ref "Q16") (pin "3") (pinfunction "C_3") (pintype "unspecified"))
    )
    (net (code "23") (name "Net-(D17-A)") (class "Default")
      (node (ref "D17") (pin "2") (pinfunction "A_2") (pintype "unspecified"))
      (node (ref "K17") (pin "4") (pinfunction "4_4") (pintype "input"))
      (node (ref "Q17") (pin "3") (pinfunction "C_3") (pintype "unspecified"))
    )
    (net (code "24") (name "Net-(D18-A)") (class "Default")
      (node (ref "D18") (pin "2") (pinfunction "A_2") (pintype "unspecified"))
      (node (ref "K18") (pin "4") (pinfunction "4_4") (pintype "input"))
      (node (ref "Q18") (pin "3") (pinfunction "C_3") (pintype "unspecified"))
    )
    (net (code "25") (name "Net-(D19-A)") (class "Default")
      (node (ref "D19") (pin "2") (pinfunction "A_2") (pintype "unspecified"))
      (node (ref "K19") (pin "4") (pinfunction "4_4") (pintype "input"))
      (node (ref "Q19") (pin "3") (pinfunction "C_3") (pintype "unspecified"))
    )
    (net (code "26") (name "Net-(D20-A)") (class "Default")
      (node (ref "D20") (pin "2") (pinfunction "A_2") (pintype "unspecified"))
      (node (ref "K20") (pin "4") (pinfunction "4_4") (pintype "input"))
      (node (ref "Q20") (pin "3") (pinfunction "C_3") (pintype "unspecified"))
    )
    (net (code "27") (name "Net-(D21-A)") (class "Default")
      (node (ref "D21") (pin "2") (pinfunction "A_2") (pintype "unspecified"))
      (node (ref "K21") (pin "4") (pinfunction "4_4") (pintype "input"))
      (node (ref "Q21") (pin "3") (pinfunction "C_3") (pintype "unspecified"))
    )
    (net (code "28") (name "Net-(D22-A)") (class "Default")
      (node (ref "D22") (pin "2") (pinfunction "A_2") (pintype "unspecified"))
      (node (ref "K22") (pin "4") (pinfunction "4_4") (pintype "input"))
      (node (ref "Q22") (pin "3") (pinfunction "C_3") (pintype "unspecified"))
    )
    (net (code "29") (name "Net-(D23-A)") (class "Default")
      (node (ref "D23") (pin "2") (pinfunction "A_2") (pintype "unspecified"))
      (node (ref "K23") (pin "4") (pinfunction "4_4") (pintype "input"))
      (node (ref "Q23") (pin "3") (pinfunction "C_3") (pintype "unspecified"))
    )
    (net (code "30") (name "Net-(D24-A)") (class "Default")
      (node (ref "D24") (pin "2") (pinfunction "A_2") (pintype "unspecified"))
      (node (ref "K24") (pin "4") (pinfunction "4_4") (pintype "input"))
      (node (ref "Q24") (pin "3") (pinfunction "C_3") (pintype "unspecified"))
    )
    (net (code "31") (name "Net-(D25-A)") (class "Default")
      (node (ref "D25") (pin "2") (pinfunction "A_2") (pintype "unspecified"))
      (node (ref "P17") (pin "1") (pinfunction "1_1") (pintype "input"))
    )
    (net (code "32") (name "Net-(D25-K)") (class "Default")
      (node (ref "C3") (pin "1") (pinfunction "1_1") (pintype "unspecified"))
      (node (ref "D25") (pin "1") (pinfunction "K_1") (pintype "unspecified"))
      (node (ref "U2") (pin "1") (pinfunction "IN_1") (pintype "unspecified"))
    )
    (net (code "33") (name "Net-(K1-Pad2)") (class "Default")
      (node (ref "K1") (pin "2") (pinfunction "2_2") (pintype "input"))
      (node (ref "U3") (pin "1") (pinfunction "1_1") (pintype "unspecified"))
    )
    (net (code "34") (name "Net-(K2-Pad2)") (class "Default")
      (node (ref "K2") (pin "2") (pinfunction "2_2") (pintype "input"))
      (node (ref "U3") (pin "2") (pinfunction "2_2") (pintype "unspecified"))
    )
    (net (code "35") (name "Net-(K3-Pad2)") (class "Default")
      (node (ref "K3") (pin "2") (pinfunction "2_2") (pintype "input"))
      (node (ref "U4") (pin "2") (pinfunction "2_2") (pintype "unspecified"))
    )
    (net (code "36") (name "Net-(K4-Pad2)") (class "Default")
      (node (ref "K4") (pin "2") (pinfunction "2_2") (pintype "input"))
      (node (ref "U4") (pin "1") (pinfunction "1_1") (pintype "unspecified"))
    )
    (net (code "37") (name "Net-(K5-Pad2)") (class "Default")
      (node (ref "K5") (pin "2") (pinfunction "2_2") (pintype "input"))
      (node (ref "U5") (pin "2") (pinfunction "2_2") (pintype "unspecified"))
    )
    (net (code "38") (name "Net-(K6-Pad2)") (class "Default")
      (node (ref "K6") (pin "2") (pinfunction "2_2") (pintype "input"))
      (node (ref "U5") (pin "1") (pinfunction "1_1") (pintype "unspecified"))
    )
    (net (code "39") (name "Net-(K7-Pad2)") (class "Default")
      (node (ref "K7") (pin "2") (pinfunction "2_2") (pintype "input"))
      (node (ref "U6") (pin "2") (pinfunction "2_2") (pintype "unspecified"))
    )
    (net (code "40") (name "Net-(K8-Pad2)") (class "Default")
      (node (ref "K8") (pin "2") (pinfunction "2_2") (pintype "input"))
      (node (ref "U6") (pin "1") (pinfunction "1_1") (pintype "unspecified"))
    )
    (net (code "41") (name "Net-(K9-Pad2)") (class "Default")
      (node (ref "K9") (pin "2") (pinfunction "2_2") (pintype "input"))
      (node (ref "U7") (pin "2") (pinfunction "2_2") (pintype "unspecified"))
    )
    (net (code "42") (name "Net-(K10-Pad2)") (class "Default")
      (node (ref "K10") (pin "2") (pinfunction "2_2") (pintype "input"))
      (node (ref "U7") (pin "1") (pinfunction "1_1") (pintype "unspecified"))
    )
    (net (code "43") (name "Net-(K11-Pad2)") (class "Default")
      (node (ref "K11") (pin "2") (pinfunction "2_2") (pintype "input"))
      (node (ref "U8") (pin "1") (pinfunction "1_1") (pintype "unspecified"))
    )
    (net (code "44") (name "Net-(K12-Pad2)") (class "Default")
      (node (ref "K12") (pin "2") (pinfunction "2_2") (pintype "input"))
      (node (ref "U8") (pin "2") (pinfunction "2_2") (pintype "unspecified"))
    )
    (net (code "45") (name "Net-(K13-Pad2)") (class "Default")
      (node (ref "K13") (pin "2") (pinfunction "2_2") (pintype "input"))
      (node (ref "U9") (pin "1") (pinfunction "1_1") (pintype "unspecified"))
    )
    (net (code "46") (name "Net-(K14-Pad2)") (class "Default")
      (node (ref "K14") (pin "2") (pinfunction "2_2") (pintype "input"))
      (node (ref "U9") (pin "2") (pinfunction "2_2") (pintype "unspecified"))
    )
    (net (code "47") (name "Net-(K15-Pad2)") (class "Default")
      (node (ref "K15") (pin "2") (pinfunction "2_2") (pintype "input"))
      (node (ref "U10") (pin "1") (pinfunction "1_1") (pintype "unspecified"))
    )
    (net (code "48") (name "Net-(K16-Pad2)") (class "Default")
      (node (ref "K16") (pin "2") (pinfunction "2_2") (pintype "input"))
      (node (ref "U10") (pin "2") (pinfunction "2_2") (pintype "unspecified"))
    )
    (net (code "49") (name "Net-(K17-Pad2)") (class "Default")
      (node (ref "K17") (pin "2") (pinfunction "2_2") (pintype "input"))
      (node (ref "U11") (pin "1") (pinfunction "1_1") (pintype "unspecified"))
    )
    (net (code "50") (name "Net-(K18-Pad2)") (class "Default")
      (node (ref "K18") (pin "2") (pinfunction "2_2") (pintype "input"))
      (node (ref "U11") (pin "2") (pinfunction "2_2") (pintype "unspecified"))
    )
    (net (code "51") (name "Net-(K19-Pad2)") (class "Default")
      (node (ref "K19") (pin "2") (pinfunction "2_2") (pintype "input"))
      (node (ref "U12") (pin "1") (pinfunction "1_1") (pintype "unspecified"))
    )
    (net (code "52") (name "Net-(K20-Pad2)") (class "Default")
      (node (ref "K20") (pin "2") (pinfunction "2_2") (pintype "input"))
      (node (ref "U12") (pin "2") (pinfunction "2_2") (pintype "unspecified"))
    )
    (net (code "53") (name "Net-(K21-Pad2)") (class "Default")
      (node (ref "K21") (pin "2") (pinfunction "2_2") (pintype "input"))
      (node (ref "U13") (pin "1") (pinfunction "1_1") (pintype "unspecified"))
    )
    (net (code "54") (name "Net-(K22-Pad2)") (class "Default")
      (node (ref "K22") (pin "2") (pinfunction "2_2") (pintype "input"))
      (node (ref "U13") (pin "2") (pinfunction "2_2") (pintype "unspecified"))
    )
    (net (code "55") (name "Net-(K23-Pad2)") (class "Default")
      (node (ref "K23") (pin "2") (pinfunction "2_2") (pintype "input"))
      (node (ref "U14") (pin "1") (pinfunction "1_1") (pintype "unspecified"))
    )
    (net (code "56") (name "Net-(K24-Pad2)") (class "Default")
      (node (ref "K24") (pin "2") (pinfunction "2_2") (pintype "input"))
      (node (ref "U14") (pin "2") (pinfunction "2_2") (pintype "unspecified"))
    )
    (net (code "57") (name "Net-(LD1-Pad2)") (class "Default")
      (node (ref "LD1") (pin "2") (pinfunction "2_2") (pintype "unspecified"))
      (node (ref "R24") (pin "1") (pinfunction "1_1") (pintype "unspecified"))
    )
    (net (code "58") (name "Net-(Q1-B)") (class "Default")
      (node (ref "Q1") (pin "2") (pinfunction "B_2") (pintype "unspecified"))
      (node (ref "R1") (pin "1") (pinfunction "1_1") (pintype "unspecified"))
    )
    (net (code "59") (name "Net-(Q2-B)") (class "Default")
      (node (ref "Q2") (pin "2") (pinfunction "B_2") (pintype "unspecified"))
      (node (ref "R2") (pin "1") (pinfunction "1_1") (pintype "unspecified"))
    )
    (net (code "60") (name "Net-(Q3-B)") (class "Default")
      (node (ref "Q3") (pin "2") (pinfunction "B_2") (pintype "unspecified"))
      (node (ref "R3") (pin "1") (pinfunction "1_1") (pintype "unspecified"))
    )
    (net (code "61") (name "Net-(Q4-B)") (class "Default")
      (node (ref "Q4") (pin "2") (pinfunction "B_2") (pintype "unspecified"))
      (node (ref "R4") (pin "1") (pinfunction "1_1") (pintype "unspecified"))
    )
    (net (code "62") (name "Net-(Q5-B)") (class "Default")
      (node (ref "Q5") (pin "2") (pinfunction "B_2") (pintype "unspecified"))
      (node (ref "R5") (pin "1") (pinfunction "1_1") (pintype "unspecified"))
    )
    (net (code "63") (name "Net-(Q6-B)") (class "Default")
      (node (ref "Q6") (pin "2") (pinfunction "B_2") (pintype "unspecified"))
      (node (ref "R6") (pin "1") (pinfunction "1_1") (pintype "unspecified"))
    )
    (net (code "64") (name "Net-(Q7-B)") (class "Default")
      (node (ref "Q7") (pin "2") (pinfunction "B_2") (pintype "unspecified"))
      (node (ref "R7") (pin "1") (pinfunction "1_1") (pintype "unspecified"))
    )
    (net (code "65") (name "Net-(Q8-B)") (class "Default")
      (node (ref "Q8") (pin "2") (pinfunction "B_2") (pintype "unspecified"))
      (node (ref "R8") (pin "1") (pinfunction "1_1") (pintype "unspecified"))
    )
    (net (code "66") (name "Net-(Q9-B)") (class "Default")
      (node (ref "Q9") (pin "2") (pinfunction "B_2") (pintype "unspecified"))
      (node (ref "R9") (pin "1") (pinfunction "1_1") (pintype "unspecified"))
    )
    (net (code "67") (name "Net-(Q10-B)") (class "Default")
      (node (ref "Q10") (pin "2") (pinfunction "B_2") (pintype "unspecified"))
      (node (ref "R10") (pin "1") (pinfunction "1_1") (pintype "unspecified"))
    )
    (net (code "68") (name "Net-(Q11-B)") (class "Default")
      (node (ref "Q11") (pin "2") (pinfunction "B_2") (pintype "unspecified"))
      (node (ref "R11") (pin "1") (pinfunction "1_1") (pintype "unspecified"))
    )
    (net (code "69") (name "Net-(Q12-B)") (class "Default")
      (node (ref "Q12") (pin "2") (pinfunction "B_2") (pintype "unspecified"))
      (node (ref "R12") (pin "1") (pinfunction "1_1") (pintype "unspecified"))
    )
    (net (code "70") (name "Net-(Q13-B)") (class "Default")
      (node (ref "Q13") (pin "2") (pinfunction "B_2") (pintype "unspecified"))
      (node (ref "R13") (pin "1") (pinfunction "1_1") (pintype "unspecified"))
    )
    (net (code "71") (name "Net-(Q14-B)") (class "Default")
      (node (ref "Q14") (pin "2") (pinfunction "B_2") (pintype "unspecified"))
      (node (ref "R14") (pin "1") (pinfunction "1_1") (pintype "unspecified"))
    )
    (net (code "72") (name "Net-(Q15-B)") (class "Default")
      (node (ref "Q15") (pin "2") (pinfunction "B_2") (pintype "unspecified"))
      (node (ref "R15") (pin "1") (pinfunction "1_1") (pintype "unspecified"))
    )
    (net (code "73") (name "Net-(Q16-B)") (class "Default")
      (node (ref "Q16") (pin "2") (pinfunction "B_2") (pintype "unspecified"))
      (node (ref "R16") (pin "1") (pinfunction "1_1") (pintype "unspecified"))
    )
    (net (code "74") (name "Net-(Q17-B)") (class "Default")
      (node (ref "Q17") (pin "2") (pinfunction "B_2") (pintype "unspecified"))
      (node (ref "R17") (pin "1") (pinfunction "1_1") (pintype "unspecified"))
    )
    (net (code "75") (name "Net-(Q18-B)") (class "Default")
      (node (ref "Q18") (pin "2") (pinfunction "B_2") (pintype "unspecified"))
      (node (ref "R18") (pin "1") (pinfunction "1_1") (pintype "unspecified"))
    )
    (net (code "76") (name "Net-(Q19-B)") (class "Default")
      (node (ref "Q19") (pin "2") (pinfunction "B_2") (pintype "unspecified"))
      (node (ref "R19") (pin "1") (pinfunction "1_1") (pintype "unspecified"))
    )
    (net (code "77") (name "Net-(Q20-B)") (class "Default")
      (node (ref "Q20") (pin "2") (pinfunction "B_2") (pintype "unspecified"))
      (node (ref "R20") (pin "1") (pinfunction "1_1") (pintype "unspecified"))
    )
    (net (code "78") (name "Net-(Q21-B)") (class "Default")
      (node (ref "Q21") (pin "2") (pinfunction "B_2") (pintype "unspecified"))
      (node (ref "R21") (pin "1") (pinfunction "1_1") (pintype "unspecified"))
    )
    (net (code "79") (name "Net-(Q22-B)") (class "Default")
      (node (ref "Q22") (pin "2") (pinfunction "B_2") (pintype "unspecified"))
      (node (ref "R22") (pin "1") (pinfunction "1_1") (pintype "unspecified"))
    )
    (net (code "80") (name "Net-(Q23-B)") (class "Default")
      (node (ref "Q23") (pin "2") (pinfunction "B_2") (pintype "unspecified"))
      (node (ref "R23") (pin "1") (pinfunction "1_1") (pintype "unspecified"))
    )
    (net (code "81") (name "Net-(Q24-B)") (class "Default")
      (node (ref "Q24") (pin "2") (pinfunction "B_2") (pintype "unspecified"))
      (node (ref "R26") (pin "1") (pinfunction "1_1") (pintype "unspecified"))
    )
    (net (code "82") (name "Net-(R28-Pad2)") (class "Default")
      (node (ref "R28") (pin "2") (pinfunction "2_2") (pintype "unspecified"))
      (node (ref "R29") (pin "1") (pinfunction "1_1") (pintype "unspecified"))
    )
    (net (code "83") (name "Net-(U1-PB6_XTAL1)") (class "Default")
      (node (ref "C1") (pin "2") (pinfunction "2_2") (pintype "unspecified"))
      (node (ref "U1") (pin "9") (pinfunction "PB6_XTAL1_9") (pintype "bidirectional"))
      (node (ref "X1") (pin "1") (pinfunction "1_1") (pintype "unspecified"))
    )
    (net (code "84") (name "Net-(U1-PB7_XTAL2)") (class "Default")
      (node (ref "C2") (pin "2") (pinfunction "2_2") (pintype "unspecified"))
      (node (ref "U1") (pin "10") (pinfunction "PB7_XTAL2_10") (pintype "bidirectional"))
      (node (ref "X1") (pin "2") (pinfunction "2_2") (pintype "unspecified"))
    )
    (net (code "85") (name "Net-(U1-PC6_RESET#)") (class "Default")
      (node (ref "KEY1") (pin "3") (pinfunction "3_3") (pintype "input"))
      (node (ref "KEY1") (pin "4") (pinfunction "4_4") (pintype "input"))
      (node (ref "R25") (pin "1") (pinfunction "1_1") (pintype "unspecified"))
      (node (ref "U1") (pin "1") (pinfunction "PC6_RESET#_1") (pintype "bidirectional"))
    )
    (net (code "86") (name "Net-(U1-PCINT5_PB5)") (class "Default")
      (node (ref "LD1") (pin "1") (pinfunction "1_1") (pintype "unspecified"))
      (node (ref "U1") (pin "19") (pinfunction "PCINT5_PB5_19") (pintype "bidirectional"))
    )
    (net (code "87") (name "Net-(U15-ADJUST)") (class "Default")
      (node (ref "R27") (pin "1") (pinfunction "1_1") (pintype "unspecified"))
      (node (ref "R28") (pin "1") (pinfunction "1_1") (pintype "unspecified"))
      (node (ref "U15") (pin "1") (pinfunction "ADJUST_1") (pintype "unspecified"))
    )
    (net (code "88") (name "Net-(U16-UD+)") (class "Default")
      (node (ref "U16") (pin "5") (pinfunction "UD+_5") (pintype "unspecified"))
      (node (ref "USB1") (pin "3") (pinfunction "D+_3") (pintype "input"))
    )
    (net (code "89") (name "Net-(U16-UD-)") (class "Default")
      (node (ref "U16") (pin "6") (pinfunction "UD-_6") (pintype "unspecified"))
      (node (ref "USB1") (pin "2") (pinfunction "D-_2") (pintype "input"))
    )
    (net (code "90") (name "Net-(U16-V3)") (class "Default")
      (node (ref "C7") (pin "1") (pinfunction "1_1") (pintype "unspecified"))
      (node (ref "U16") (pin "4") (pinfunction "V3_4") (pintype "unspecified"))
    )
    (net (code "91") (name "Net-(U16-VCC)") (class "Default")
      (node (ref "U16") (pin "16") (pinfunction "VCC_16") (pintype "unspecified"))
      (node (ref "USB1") (pin "1") (pinfunction "VCC_1") (pintype "input"))
    )
    (net (code "92") (name "Net-(U16-XI)") (class "Default")
      (node (ref "C8") (pin "2") (pinfunction "2_2") (pintype "unspecified"))
      (node (ref "U16") (pin "7") (pinfunction "XI_7") (pintype "unspecified"))
      (node (ref "X2") (pin "1") (pinfunction "OSC1_1") (pintype "input"))
    )
    (net (code "93") (name "Net-(U16-XO)") (class "Default")
      (node (ref "C9") (pin "2") (pinfunction "2_2") (pintype "unspecified"))
      (node (ref "U16") (pin "8") (pinfunction "XO_8") (pintype "unspecified"))
      (node (ref "X2") (pin "2") (pinfunction "OSC2_2") (pintype "input"))
    )
    (net (code "94") (name "channel1") (class "Default")
      (node (ref "R1") (pin "2") (pinfunction "2_2") (pintype "unspecified"))
      (node (ref "R2") (pin "2") (pinfunction "2_2") (pintype "unspecified"))
      (node (ref "U1") (pin "4") (pinfunction "INT0_PD2_4") (pintype "bidirectional"))
    )
    (net (code "95") (name "channel2") (class "Default")
      (node (ref "R3") (pin "2") (pinfunction "2_2") (pintype "unspecified"))
      (node (ref "R4") (pin "2") (pinfunction "2_2") (pintype "unspecified"))
      (node (ref "U1") (pin "5") (pinfunction "INT1_PD3_5") (pintype "bidirectional"))
    )
    (net (code "96") (name "channel3") (class "Default")
      (node (ref "R5") (pin "2") (pinfunction "2_2") (pintype "unspecified"))
      (node (ref "R6") (pin "2") (pinfunction "2_2") (pintype "unspecified"))
      (node (ref "U1") (pin "6") (pinfunction "T0_PD4_6") (pintype "bidirectional"))
    )
    (net (code "97") (name "channel4") (class "Default")
      (node (ref "R7") (pin "2") (pinfunction "2_2") (pintype "unspecified"))
      (node (ref "R8") (pin "2") (pinfunction "2_2") (pintype "unspecified"))
      (node (ref "U1") (pin "11") (pinfunction "T1_PD5_11") (pintype "bidirectional"))
    )
    (net (code "98") (name "channel5") (class "Default")
      (node (ref "R10") (pin "2") (pinfunction "2_2") (pintype "unspecified"))
      (node (ref "R9") (pin "2") (pinfunction "2_2") (pintype "unspecified"))
      (node (ref "U1") (pin "12") (pinfunction "AIN0_PD6_12") (pintype "bidirectional"))
    )
    (net (code "99") (name "channel6") (class "Default")
      (node (ref "R11") (pin "2") (pinfunction "2_2") (pintype "unspecified"))
      (node (ref "R12") (pin "2") (pinfunction "2_2") (pintype "unspecified"))
      (node (ref "U1") (pin "13") (pinfunction "AIN1_PD7_13") (pintype "bidirectional"))
    )
    (net (code "100") (name "channel7") (class "Default")
      (node (ref "R13") (pin "2") (pinfunction "2_2") (pintype "unspecified"))
      (node (ref "R14") (pin "2") (pinfunction "2_2") (pintype "unspecified"))
      (node (ref "U1") (pin "14") (pinfunction "PCINT0_PB0_14") (pintype "bidirectional"))
    )
    (net (code "101") (name "channel8") (class "Default")
      (node (ref "R15") (pin "2") (pinfunction "2_2") (pintype "unspecified"))
      (node (ref "R16") (pin "2") (pinfunction "2_2") (pintype "unspecified"))
      (node (ref "U1") (pin "15") (pinfunction "PCINT1__PB1_15") (pintype "bidirectional"))
    )
    (net (code "102") (name "channel9") (class "Default")
      (node (ref "R17") (pin "2") (pinfunction "2_2") (pintype "unspecified"))
      (node (ref "R18") (pin "2") (pinfunction "2_2") (pintype "unspecified"))
      (node (ref "U1") (pin "16") (pinfunction "PCINT2_PB2_16") (pintype "bidirectional"))
    )
    (net (code "103") (name "channel10") (class "Default")
      (node (ref "R19") (pin "2") (pinfunction "2_2") (pintype "unspecified"))
      (node (ref "R20") (pin "2") (pinfunction "2_2") (pintype "unspecified"))
      (node (ref "U1") (pin "17") (pinfunction "PCINT3_PB3_17") (pintype "bidirectional"))
    )
    (net (code "104") (name "channel11") (class "Default")
      (node (ref "R21") (pin "2") (pinfunction "2_2") (pintype "unspecified"))
      (node (ref "R22") (pin "2") (pinfunction "2_2") (pintype "unspecified"))
    )
    (net (code "105") (name "channel12") (class "Default")
      (node (ref "R23") (pin "2") (pinfunction "2_2") (pintype "unspecified"))
      (node (ref "R26") (pin "2") (pinfunction "2_2") (pintype "unspecified"))
    )
    (net (code "106") (name "eps8266 3.3V RX") (class "Default")
      (node (ref "H1") (pin "8") (pinfunction "8_8") (pintype "unspecified"))
      (node (ref "Q26") (pin "1") (pinfunction "S_1") (pintype "unspecified"))
      (node (ref "R33") (pin "1") (pinfunction "1_1") (pintype "unspecified"))
    )
    (net (code "107") (name "eps8266 3.3V TX") (class "Default")
      (node (ref "H1") (pin "1") (pinfunction "1_1") (pintype "unspecified"))
      (node (ref "Q25") (pin "1") (pinfunction "S_1") (pintype "unspecified"))
      (node (ref "R30") (pin "1") (pinfunction "1_1") (pintype "unspecified"))
    )
    (net (code "108") (name "eps8266 5V RX") (class "Default")
      (node (ref "Q26") (pin "3") (pinfunction "D_3") (pintype "unspecified"))
      (node (ref "R32") (pin "1") (pinfunction "1_1") (pintype "unspecified"))
      (node (ref "U1") (pin "24") (pinfunction "PC1_ADC1_24") (pintype "bidirectional"))
    )
    (net (code "109") (name "eps8266 5V TX") (class "Default")
      (node (ref "Q25") (pin "3") (pinfunction "D_3") (pintype "unspecified"))
      (node (ref "R31") (pin "1") (pinfunction "1_1") (pintype "unspecified"))
      (node (ref "U1") (pin "23") (pinfunction "PC0_ADC0_23") (pintype "bidirectional"))
    )
    (net (code "110") (name "line1") (class "Default")
      (node (ref "K1") (pin "5") (pinfunction "5_5") (pintype "input"))
      (node (ref "K10") (pin "5") (pinfunction "5_5") (pintype "input"))
      (node (ref "K11") (pin "5") (pinfunction "5_5") (pintype "input"))
      (node (ref "K13") (pin "5") (pinfunction "5_5") (pintype "input"))
      (node (ref "K15") (pin "5") (pinfunction "5_5") (pintype "input"))
      (node (ref "K17") (pin "5") (pinfunction "5_5") (pintype "input"))
      (node (ref "K19") (pin "5") (pinfunction "5_5") (pintype "input"))
      (node (ref "K21") (pin "5") (pinfunction "5_5") (pintype "input"))
      (node (ref "K23") (pin "5") (pinfunction "5_5") (pintype "input"))
      (node (ref "K4") (pin "5") (pinfunction "5_5") (pintype "input"))
      (node (ref "K6") (pin "5") (pinfunction "5_5") (pintype "input"))
      (node (ref "K8") (pin "5") (pinfunction "5_5") (pintype "input"))
      (node (ref "P18") (pin "1") (pinfunction "1_1") (pintype "input"))
    )
    (net (code "111") (name "line2") (class "Default")
      (node (ref "K12") (pin "5") (pinfunction "5_5") (pintype "input"))
      (node (ref "K14") (pin "5") (pinfunction "5_5") (pintype "input"))
      (node (ref "K16") (pin "5") (pinfunction "5_5") (pintype "input"))
      (node (ref "K18") (pin "5") (pinfunction "5_5") (pintype "input"))
      (node (ref "K2") (pin "5") (pinfunction "5_5") (pintype "input"))
      (node (ref "K20") (pin "5") (pinfunction "5_5") (pintype "input"))
      (node (ref "K22") (pin "5") (pinfunction "5_5") (pintype "input"))
      (node (ref "K24") (pin "5") (pinfunction "5_5") (pintype "input"))
      (node (ref "K3") (pin "5") (pinfunction "5_5") (pintype "input"))
      (node (ref "K5") (pin "5") (pinfunction "5_5") (pintype "input"))
      (node (ref "K7") (pin "5") (pinfunction "5_5") (pintype "input"))
      (node (ref "K9") (pin "5") (pinfunction "5_5") (pintype "input"))
      (node (ref "P18") (pin "2") (pinfunction "2_2") (pintype "input"))
    )
    (net (code "112") (name "unconnected-(H1-Pad3)") (class "Default")
      (node (ref "H1") (pin "3") (pinfunction "3_3") (pintype "unspecified+no_connect"))
    )
    (net (code "113") (name "unconnected-(H1-Pad4)") (class "Default")
      (node (ref "H1") (pin "4") (pinfunction "4_4") (pintype "unspecified+no_connect"))
    )
    (net (code "114") (name "unconnected-(H1-Pad5)") (class "Default")
      (node (ref "H1") (pin "5") (pinfunction "5_5") (pintype "unspecified+no_connect"))
    )
    (net (code "115") (name "unconnected-(H1-Pad6)") (class "Default")
      (node (ref "H1") (pin "6") (pinfunction "6_6") (pintype "unspecified+no_connect"))
    )
    (net (code "116") (name "unconnected-(K1-Pad3)") (class "Default")
      (node (ref "K1") (pin "3") (pinfunction "3_3") (pintype "input+no_connect"))
    )
    (net (code "117") (name "unconnected-(K2-Pad3)") (class "Default")
      (node (ref "K2") (pin "3") (pinfunction "3_3") (pintype "input+no_connect"))
    )
    (net (code "118") (name "unconnected-(K3-Pad3)") (class "Default")
      (node (ref "K3") (pin "3") (pinfunction "3_3") (pintype "input+no_connect"))
    )
    (net (code "119") (name "unconnected-(K4-Pad3)") (class "Default")
      (node (ref "K4") (pin "3") (pinfunction "3_3") (pintype "input+no_connect"))
    )
    (net (code "120") (name "unconnected-(K5-Pad3)") (class "Default")
      (node (ref "K5") (pin "3") (pinfunction "3_3") (pintype "input+no_connect"))
    )
    (net (code "121") (name "unconnected-(K6-Pad3)") (class "Default")
      (node (ref "K6") (pin "3") (pinfunction "3_3") (pintype "input+no_connect"))
    )
    (net (code "122") (name "unconnected-(K7-Pad3)") (class "Default")
      (node (ref "K7") (pin "3") (pinfunction "3_3") (pintype "input+no_connect"))
    )
    (net (code "123") (name "unconnected-(K8-Pad3)") (class "Default")
      (node (ref "K8") (pin "3") (pinfunction "3_3") (pintype "input+no_connect"))
    )
    (net (code "124") (name "unconnected-(K9-Pad3)") (class "Default")
      (node (ref "K9") (pin "3") (pinfunction "3_3") (pintype "input+no_connect"))
    )
    (net (code "125") (name "unconnected-(K10-Pad3)") (class "Default")
      (node (ref "K10") (pin "3") (pinfunction "3_3") (pintype "input+no_connect"))
    )
    (net (code "126") (name "unconnected-(K11-Pad3)") (class "Default")
      (node (ref "K11") (pin "3") (pinfunction "3_3") (pintype "input+no_connect"))
    )
    (net (code "127") (name "unconnected-(K12-Pad3)") (class "Default")
      (node (ref "K12") (pin "3") (pinfunction "3_3") (pintype "input+no_connect"))
    )
    (net (code "128") (name "unconnected-(K13-Pad3)") (class "Default")
      (node (ref "K13") (pin "3") (pinfunction "3_3") (pintype "input+no_connect"))
    )
    (net (code "129") (name "unconnected-(K14-Pad3)") (class "Default")
      (node (ref "K14") (pin "3") (pinfunction "3_3") (pintype "input+no_connect"))
    )
    (net (code "130") (name "unconnected-(K15-Pad3)") (class "Default")
      (node (ref "K15") (pin "3") (pinfunction "3_3") (pintype "input+no_connect"))
    )
    (net (code "131") (name "unconnected-(K16-Pad3)") (class "Default")
      (node (ref "K16") (pin "3") (pinfunction "3_3") (pintype "input+no_connect"))
    )
    (net (code "132") (name "unconnected-(K17-Pad3)") (class "Default")
      (node (ref "K17") (pin "3") (pinfunction "3_3") (pintype "input+no_connect"))
    )
    (net (code "133") (name "unconnected-(K18-Pad3)") (class "Default")
      (node (ref "K18") (pin "3") (pinfunction "3_3") (pintype "input+no_connect"))
    )
    (net (code "134") (name "unconnected-(K19-Pad3)") (class "Default")
      (node (ref "K19") (pin "3") (pinfunction "3_3") (pintype "input+no_connect"))
    )
    (net (code "135") (name "unconnected-(K20-Pad3)") (class "Default")
      (node (ref "K20") (pin "3") (pinfunction "3_3") (pintype "input+no_connect"))
    )
    (net (code "136") (name "unconnected-(K21-Pad3)") (class "Default")
      (node (ref "K21") (pin "3") (pinfunction "3_3") (pintype "input+no_connect"))
    )
    (net (code "137") (name "unconnected-(K22-Pad3)") (class "Default")
      (node (ref "K22") (pin "3") (pinfunction "3_3") (pintype "input+no_connect"))
    )
    (net (code "138") (name "unconnected-(K23-Pad3)") (class "Default")
      (node (ref "K23") (pin "3") (pinfunction "3_3") (pintype "input+no_connect"))
    )
    (net (code "139") (name "unconnected-(K24-Pad3)") (class "Default")
      (node (ref "K24") (pin "3") (pinfunction "3_3") (pintype "input+no_connect"))
    )
    (net (code "140") (name "unconnected-(U1-AREF-Pad21)") (class "Default")
      (node (ref "U1") (pin "21") (pinfunction "AREF_21") (pintype "passive+no_connect"))
    )
    (net (code "141") (name "unconnected-(U1-PC2_ADC2-Pad25)") (class "Default")
      (node (ref "U1") (pin "25") (pinfunction "PC2_ADC2_25") (pintype "bidirectional+no_connect"))
    )
    (net (code "142") (name "unconnected-(U1-PC3_ADC3-Pad26)") (class "Default")
      (node (ref "U1") (pin "26") (pinfunction "PC3_ADC3_26") (pintype "bidirectional+no_connect"))
    )
    (net (code "143") (name "unconnected-(U1-PC4_ADC4-Pad27)") (class "Default")
      (node (ref "U1") (pin "27") (pinfunction "PC4_ADC4_27") (pintype "bidirectional+no_connect"))
    )
    (net (code "144") (name "unconnected-(U1-PC5_ADC5-Pad28)") (class "Default")
      (node (ref "U1") (pin "28") (pinfunction "PC5_ADC5_28") (pintype "bidirectional+no_connect"))
    )
    (net (code "145") (name "unconnected-(U1-PCINT4_PB4-Pad18)") (class "Default")
      (node (ref "U1") (pin "18") (pinfunction "PCINT4_PB4_18") (pintype "bidirectional+no_connect"))
    )
    (net (code "146") (name "unconnected-(U16-CTS#-Pad9)") (class "Default")
      (node (ref "U16") (pin "9") (pinfunction "CTS#_9") (pintype "unspecified+no_connect"))
    )
    (net (code "147") (name "unconnected-(U16-DCD#-Pad12)") (class "Default")
      (node (ref "U16") (pin "12") (pinfunction "DCD#_12") (pintype "unspecified+no_connect"))
    )
    (net (code "148") (name "unconnected-(U16-DSR#-Pad10)") (class "Default")
      (node (ref "U16") (pin "10") (pinfunction "DSR#_10") (pintype "unspecified+no_connect"))
    )
    (net (code "149") (name "unconnected-(U16-DTR#-Pad13)") (class "Default")
      (node (ref "U16") (pin "13") (pinfunction "DTR#_13") (pintype "unspecified+no_connect"))
    )
    (net (code "150") (name "unconnected-(U16-R232-Pad15)") (class "Default")
      (node (ref "U16") (pin "15") (pinfunction "R232_15") (pintype "unspecified+no_connect"))
    )
    (net (code "151") (name "unconnected-(U16-RI-Pad11)") (class "Default")
      (node (ref "U16") (pin "11") (pinfunction "RI_11") (pintype "unspecified+no_connect"))
    )
    (net (code "152") (name "unconnected-(U16-RTS#-Pad14)") (class "Default")
      (node (ref "U16") (pin "14") (pinfunction "RTS#_14") (pintype "unspecified+no_connect"))
    )
    (net (code "153") (name "unconnected-(USB1-DI-Pad4)") (class "Default")
      (node (ref "USB1") (pin "4") (pinfunction "DI_4") (pintype "input+no_connect"))
    )
  )
)
